# SCH_SpotifyControllerPCB_2024-07-13.net
KiCad netlist of a schematic drawn in EasyEDA
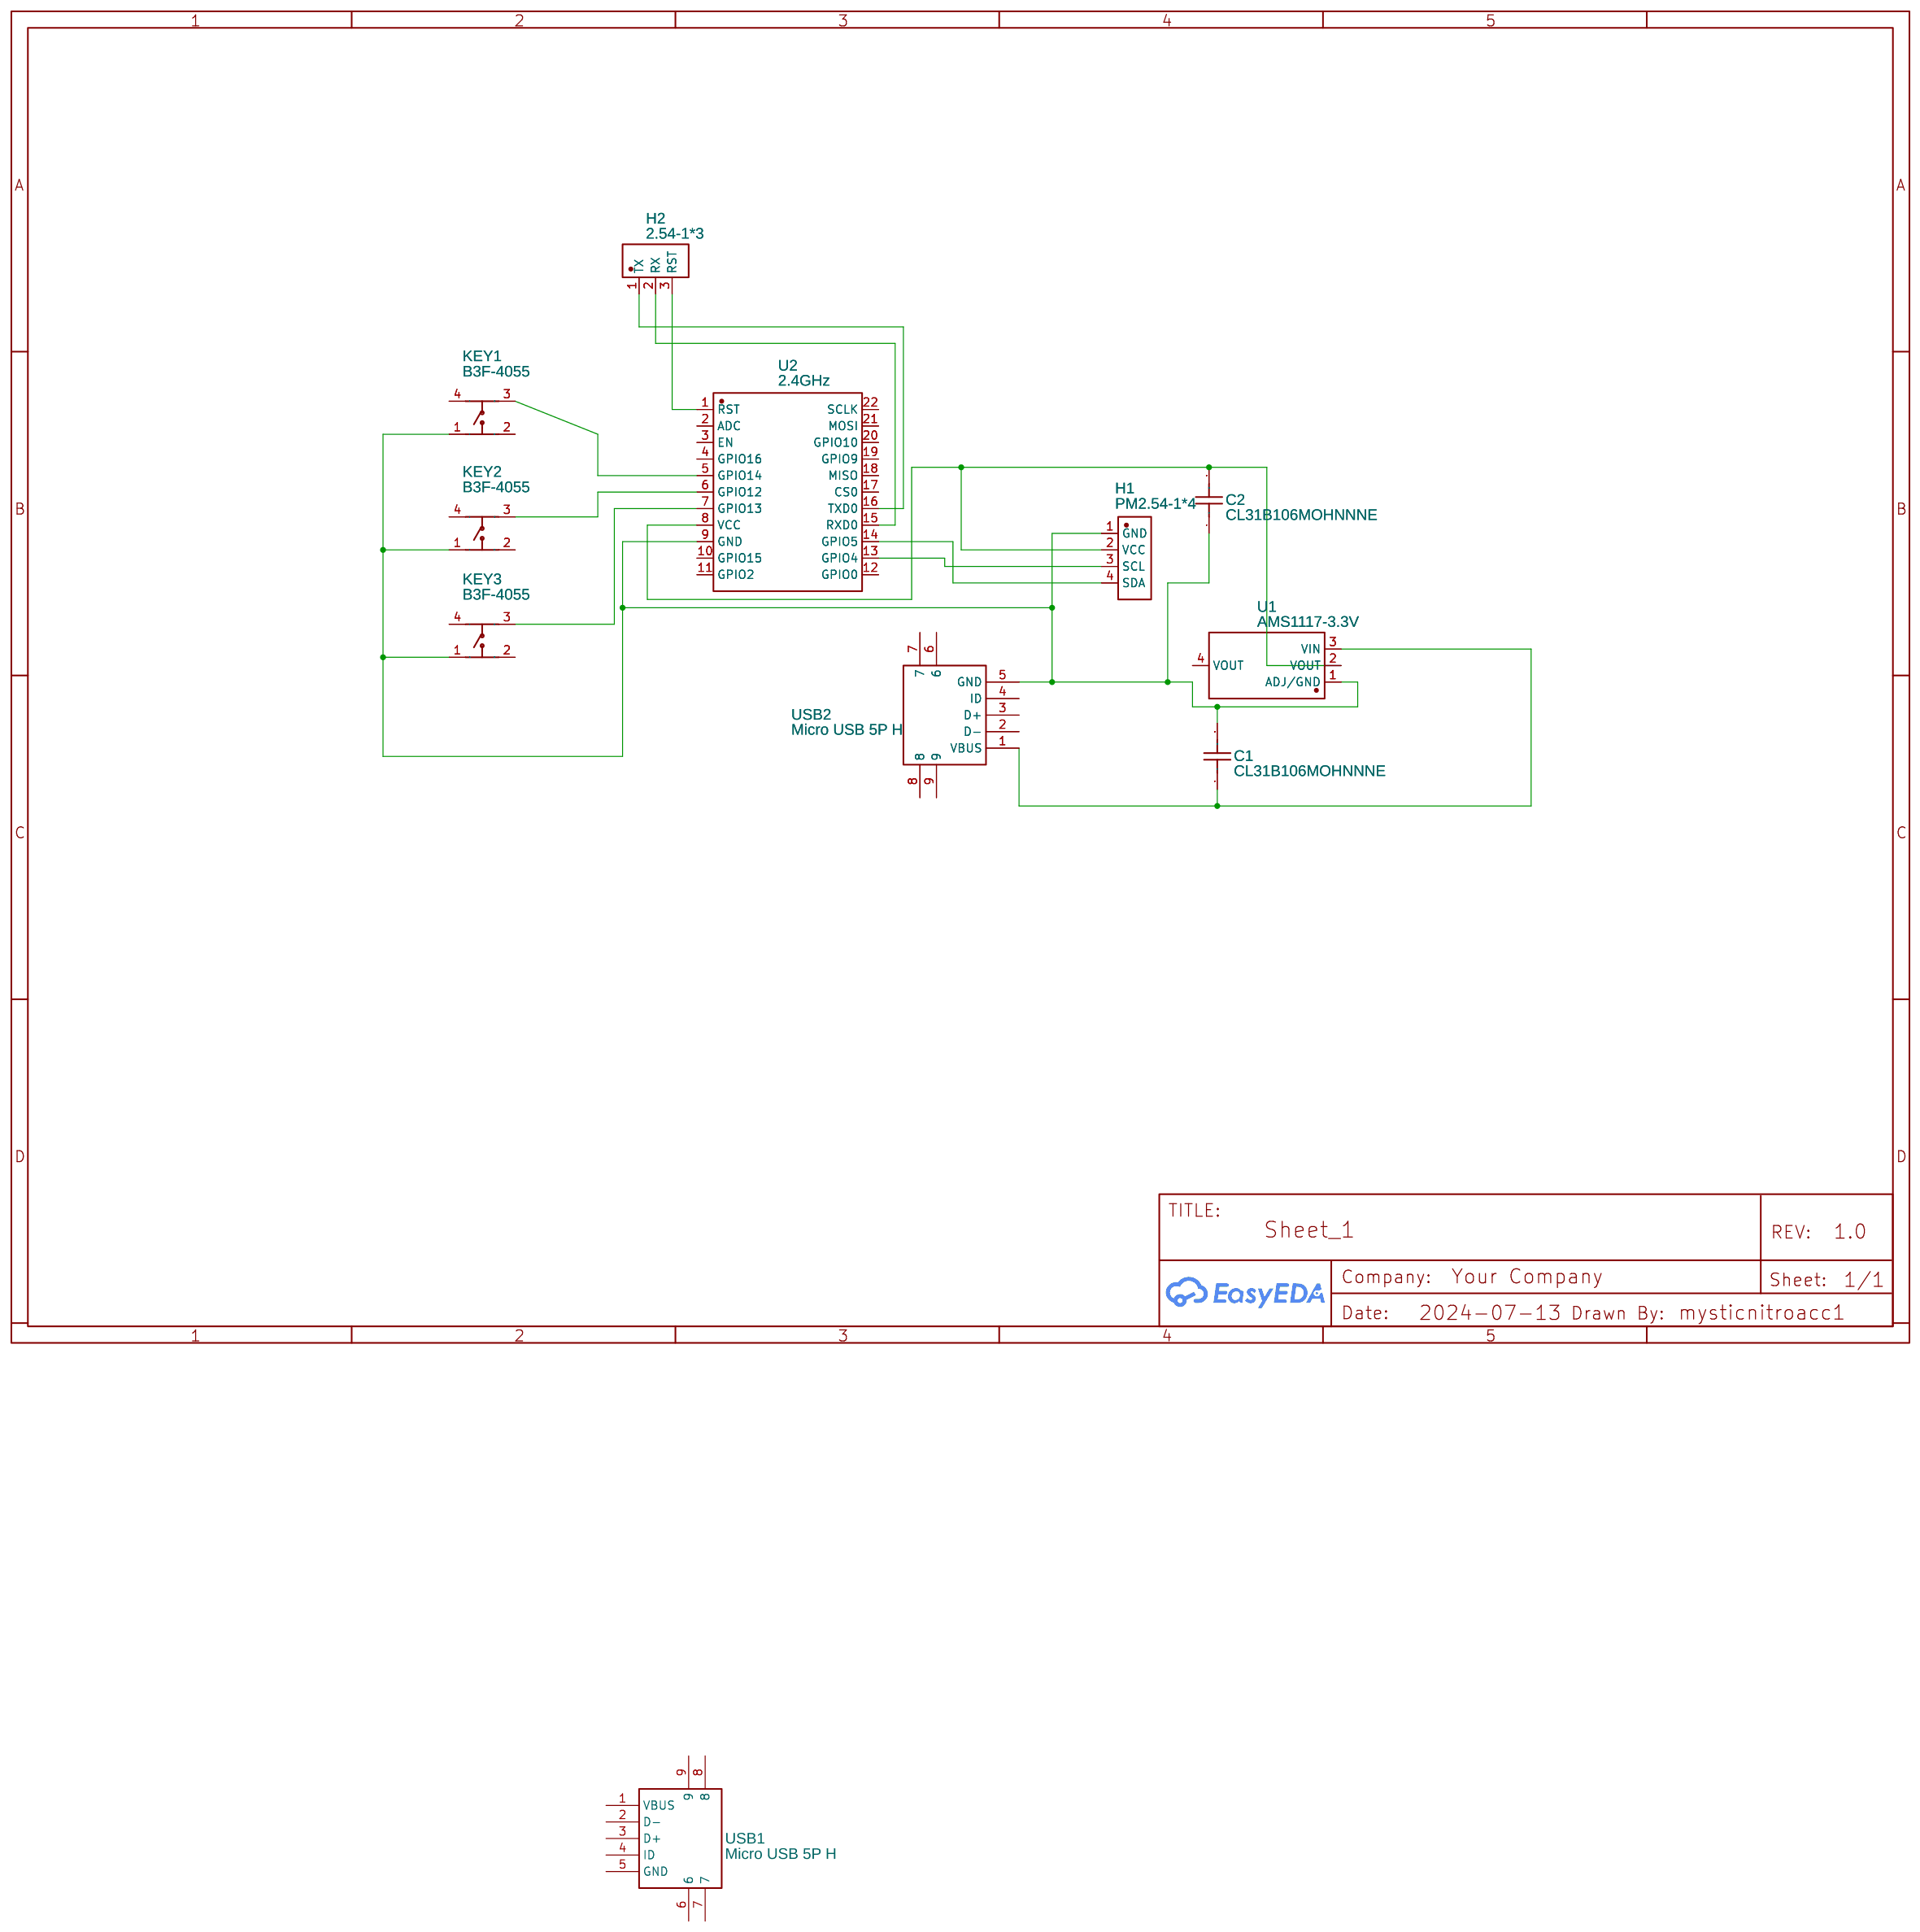
[diagram p0: schematic sheet]

(export (version "E")
  (design (tool "Eeschema 10.0.6"))
  (components
    (comp (ref "C1")
      (value "CL31B106MOHNNNE")
      (fields (field (name "Manufacturer") "Samsung Electro-Mechanics"))
      (libsource (lib "") (part "CL31B106MOHNNNE"))
    )
    (comp (ref "C2")
      (value "CL31B106MOHNNNE")
      (fields (field (name "Manufacturer") "Samsung Electro-Mechanics"))
      (libsource (lib "") (part "CL31B106MOHNNNE"))
    )
    (comp (ref "H1")
      (value "PM2.54-1*4")
      (fields (field (name "Manufacturer") "ZHOURI(洲日)"))
      (libsource (lib "") (part "PM2.54-1*4"))
    )
    (comp (ref "H2")
      (value "2.54-1*3")
      (fields (field (name "Manufacturer") "ZHOURI(洲日)"))
      (libsource (lib "") (part "2.54-1*3"))
    )
    (comp (ref "KEY1")
      (value "B3F-4055")
      (fields (field (name "Manufacturer") "OMRON(欧姆龙)"))
      (libsource (lib "") (part "B3F-4055"))
    )
    (comp (ref "KEY2")
      (value "B3F-4055")
      (fields (field (name "Manufacturer") "OMRON(欧姆龙)"))
      (libsource (lib "") (part "B3F-4055"))
    )
    (comp (ref "KEY3")
      (value "B3F-4055")
      (fields (field (name "Manufacturer") "OMRON(欧姆龙)"))
      (libsource (lib "") (part "B3F-4055"))
    )
    (comp (ref "U1")
      (value "AMS1117-3.3V")
      (fields (field (name "Manufacturer") "WPMtek(维攀)"))
      (libsource (lib "") (part "AMS1117-3.3V"))
    )
    (comp (ref "U2")
      (value "2.4GHz")
      (fields
        (field (name "Manufacturer Part") "ESP-12F(ESP8266MOD)")
        (field (name "Manufacturer") "Ai-Thinker(安信可)")
      )
      (libsource (lib "") (part "ESP-12F(ESP8266MOD)"))
    )
    (comp (ref "USB1")
      (value "Micro USB 5P H")
      (fields (field (name "Manufacturer Part") "920-E52A2021S10101") (field (name "Manufacturer") "精拓金"))
      (libsource (lib "") (part "Micro USB 5P H"))
    )
    (comp (ref "USB2")
      (value "Micro USB 5P H")
      (fields (field (name "Manufacturer Part") "920-E52A2021S10101") (field (name "Manufacturer") "精拓金"))
      (libsource (lib "") (part "Micro USB 5P H_1"))
    )
  )
  (nets
    (net (code "1") (name "Net-(H1-GND)") (class "Default")
      (node (ref "C1") (pin "2") (pinfunction "2_2") (pintype "unspecified"))
      (node (ref "C2") (pin "1") (pinfunction "1_1") (pintype "unspecified"))
      (node (ref "H1") (pin "1") (pinfunction "GND_1") (pintype "unspecified"))
      (node (ref "KEY1") (pin "1") (pinfunction "1_1") (pintype "unspecified"))
      (node (ref "KEY2") (pin "1") (pinfunction "1_1") (pintype "unspecified"))
      (node (ref "KEY3") (pin "1") (pinfunction "1_1") (pintype "unspecified"))
      (node (ref "U1") (pin "1") (pinfunction "ADJ/GND_1") (pintype "unspecified"))
      (node (ref "U2") (pin "9") (pinfunction "GND_9") (pintype "unspecified"))
      (node (ref "USB2") (pin "5") (pinfunction "GND_5") (pintype "unspecified"))
    )
    (net (code "2") (name "Net-(H1-SCL)") (class "Default")
      (node (ref "H1") (pin "3") (pinfunction "SCL_3") (pintype "unspecified"))
      (node (ref "U2") (pin "13") (pinfunction "GPIO4_13") (pintype "unspecified"))
    )
    (net (code "3") (name "Net-(H1-SDA)") (class "Default")
      (node (ref "H1") (pin "4") (pinfunction "SDA_4") (pintype "unspecified"))
      (node (ref "U2") (pin "14") (pinfunction "GPIO5_14") (pintype "unspecified"))
    )
    (net (code "4") (name "Net-(H1-VCC)") (class "Default")
      (node (ref "C2") (pin "2") (pinfunction "2_2") (pintype "unspecified"))
      (node (ref "H1") (pin "2") (pinfunction "VCC_2") (pintype "unspecified"))
      (node (ref "U1") (pin "2") (pinfunction "VOUT_2") (pintype "unspecified"))
      (node (ref "U2") (pin "8") (pinfunction "VCC_8") (pintype "unspecified"))
    )
    (net (code "5") (name "Net-(H2-RST)") (class "Default")
      (node (ref "H2") (pin "3") (pinfunction "RST_3") (pintype "unspecified"))
      (node (ref "U2") (pin "1") (pinfunction "RST_1") (pintype "unspecified"))
    )
    (net (code "6") (name "Net-(H2-RX)") (class "Default")
      (node (ref "H2") (pin "2") (pinfunction "RX_2") (pintype "unspecified"))
      (node (ref "U2") (pin "15") (pinfunction "RXD0_15") (pintype "unspecified"))
    )
    (net (code "7") (name "Net-(H2-TX)") (class "Default")
      (node (ref "H2") (pin "1") (pinfunction "TX_1") (pintype "unspecified"))
      (node (ref "U2") (pin "16") (pinfunction "TXD0_16") (pintype "unspecified"))
    )
    (net (code "8") (name "Net-(U1-VIN)") (class "Default")
      (node (ref "C1") (pin "1") (pinfunction "1_1") (pintype "unspecified"))
      (node (ref "U1") (pin "3") (pinfunction "VIN_3") (pintype "unspecified"))
      (node (ref "USB2") (pin "1") (pinfunction "VBUS_1") (pintype "unspecified"))
    )
    (net (code "9") (name "Net-(U2-GPIO12)") (class "Default")
      (node (ref "KEY2") (pin "3") (pinfunction "3_3") (pintype "unspecified"))
      (node (ref "U2") (pin "6") (pinfunction "GPIO12_6") (pintype "unspecified"))
    )
    (net (code "10") (name "Net-(U2-GPIO13)") (class "Default")
      (node (ref "KEY3") (pin "3") (pinfunction "3_3") (pintype "unspecified"))
      (node (ref "U2") (pin "7") (pinfunction "GPIO13_7") (pintype "unspecified"))
    )
    (net (code "11") (name "Net-(U2-GPIO14)") (class "Default")
      (node (ref "KEY1") (pin "3") (pinfunction "3_3") (pintype "unspecified"))
      (node (ref "U2") (pin "5") (pinfunction "GPIO14_5") (pintype "unspecified"))
    )
    (net (code "12") (name "unconnected-(KEY1-Pad2)") (class "Default")
      (node (ref "KEY1") (pin "2") (pinfunction "2_2") (pintype "unspecified"))
    )
    (net (code "13") (name "unconnected-(KEY1-Pad4)") (class "Default")
      (node (ref "KEY1") (pin "4") (pinfunction "4_4") (pintype "unspecified"))
    )
    (net (code "14") (name "unconnected-(KEY2-Pad2)") (class "Default")
      (node (ref "KEY2") (pin "2") (pinfunction "2_2") (pintype "unspecified"))
    )
    (net (code "15") (name "unconnected-(KEY2-Pad4)") (class "Default")
      (node (ref "KEY2") (pin "4") (pinfunction "4_4") (pintype "unspecified"))
    )
    (net (code "16") (name "unconnected-(KEY3-Pad2)") (class "Default")
      (node (ref "KEY3") (pin "2") (pinfunction "2_2") (pintype "unspecified"))
    )
    (net (code "17") (name "unconnected-(KEY3-Pad4)") (class "Default")
      (node (ref "KEY3") (pin "4") (pinfunction "4_4") (pintype "unspecified"))
    )
    (net (code "18") (name "unconnected-(U1-VOUT-Pad4)") (class "Default")
      (node (ref "U1") (pin "4") (pinfunction "VOUT_4") (pintype "unspecified"))
    )
    (net (code "19") (name "unconnected-(U2-ADC-Pad2)") (class "Default")
      (node (ref "U2") (pin "2") (pinfunction "ADC_2") (pintype "unspecified"))
    )
    (net (code "20") (name "unconnected-(U2-CS0-Pad17)") (class "Default")
      (node (ref "U2") (pin "17") (pinfunction "CS0_17") (pintype "unspecified"))
    )
    (net (code "21") (name "unconnected-(U2-EN-Pad3)") (class "Default")
      (node (ref "U2") (pin "3") (pinfunction "EN_3") (pintype "unspecified"))
    )
    (net (code "22") (name "unconnected-(U2-GPIO0-Pad12)") (class "Default")
      (node (ref "U2") (pin "12") (pinfunction "GPIO0_12") (pintype "unspecified"))
    )
    (net (code "23") (name "unconnected-(U2-GPIO2-Pad11)") (class "Default")
      (node (ref "U2") (pin "11") (pinfunction "GPIO2_11") (pintype "unspecified"))
    )
    (net (code "24") (name "unconnected-(U2-GPIO9-Pad19)") (class "Default")
      (node (ref "U2") (pin "19") (pinfunction "GPIO9_19") (pintype "unspecified"))
    )
    (net (code "25") (name "unconnected-(U2-GPIO10-Pad20)") (class "Default")
      (node (ref "U2") (pin "20") (pinfunction "GPIO10_20") (pintype "unspecified"))
    )
    (net (code "26") (name "unconnected-(U2-GPIO15-Pad10)") (class "Default")
      (node (ref "U2") (pin "10") (pinfunction "GPIO15_10") (pintype "unspecified"))
    )
    (net (code "27") (name "unconnected-(U2-GPIO16-Pad4)") (class "Default")
      (node (ref "U2") (pin "4") (pinfunction "GPIO16_4") (pintype "unspecified"))
    )
    (net (code "28") (name "unconnected-(U2-MISO-Pad18)") (class "Default")
      (node (ref "U2") (pin "18") (pinfunction "MISO_18") (pintype "unspecified"))
    )
    (net (code "29") (name "unconnected-(U2-MOSI-Pad21)") (class "Default")
      (node (ref "U2") (pin "21") (pinfunction "MOSI_21") (pintype "unspecified"))
    )
    (net (code "30") (name "unconnected-(U2-SCLK-Pad22)") (class "Default")
      (node (ref "U2") (pin "22") (pinfunction "SCLK_22") (pintype "unspecified"))
    )
    (net (code "31") (name "unconnected-(USB1-D+-Pad3)") (class "Default")
      (node (ref "USB1") (pin "3") (pinfunction "D+_3") (pintype "unspecified"))
    )
    (net (code "32") (name "unconnected-(USB1-D--Pad2)") (class "Default")
      (node (ref "USB1") (pin "2") (pinfunction "D-_2") (pintype "unspecified"))
    )
    (net (code "33") (name "unconnected-(USB1-GND-Pad5)") (class "Default")
      (node (ref "USB1") (pin "5") (pinfunction "GND_5") (pintype "unspecified"))
    )
    (net (code "34") (name "unconnected-(USB1-ID-Pad4)") (class "Default")
      (node (ref "USB1") (pin "4") (pinfunction "ID_4") (pintype "unspecified"))
    )
    (net (code "35") (name "unconnected-(USB1-Pad6)") (class "Default")
      (node (ref "USB1") (pin "6") (pinfunction "6_6") (pintype "unspecified"))
    )
    (net (code "36") (name "unconnected-(USB1-Pad7)") (class "Default")
      (node (ref "USB1") (pin "7") (pinfunction "7_7") (pintype "unspecified"))
    )
    (net (code "37") (name "unconnected-(USB1-Pad8)") (class "Default")
      (node (ref "USB1") (pin "8") (pinfunction "8_8") (pintype "unspecified"))
    )
    (net (code "38") (name "unconnected-(USB1-Pad9)") (class "Default")
      (node (ref "USB1") (pin "9") (pinfunction "9_9") (pintype "unspecified"))
    )
    (net (code "39") (name "unconnected-(USB1-VBUS-Pad1)") (class "Default")
      (node (ref "USB1") (pin "1") (pinfunction "VBUS_1") (pintype "unspecified"))
    )
    (net (code "40") (name "unconnected-(USB2-D+-Pad3)") (class "Default")
      (node (ref "USB2") (pin "3") (pinfunction "D+_3") (pintype "unspecified"))
    )
    (net (code "41") (name "unconnected-(USB2-D--Pad2)") (class "Default")
      (node (ref "USB2") (pin "2") (pinfunction "D-_2") (pintype "unspecified"))
    )
    (net (code "42") (name "unconnected-(USB2-ID-Pad4)") (class "Default")
      (node (ref "USB2") (pin "4") (pinfunction "ID_4") (pintype "unspecified"))
    )
    (net (code "43") (name "unconnected-(USB2-Pad6)") (class "Default")
      (node (ref "USB2") (pin "6") (pinfunction "6_6") (pintype "unspecified"))
    )
    (net (code "44") (name "unconnected-(USB2-Pad7)") (class "Default")
      (node (ref "USB2") (pin "7") (pinfunction "7_7") (pintype "unspecified"))
    )
    (net (code "45") (name "unconnected-(USB2-Pad8)") (class "Default")
      (node (ref "USB2") (pin "8") (pinfunction "8_8") (pintype "unspecified"))
    )
    (net (code "46") (name "unconnected-(USB2-Pad9)") (class "Default")
      (node (ref "USB2") (pin "9") (pinfunction "9_9") (pintype "unspecified"))
    )
  )
)
